# MKRFox1200V2_0.net
KiCad netlist of a schematic drawn in EAGLE
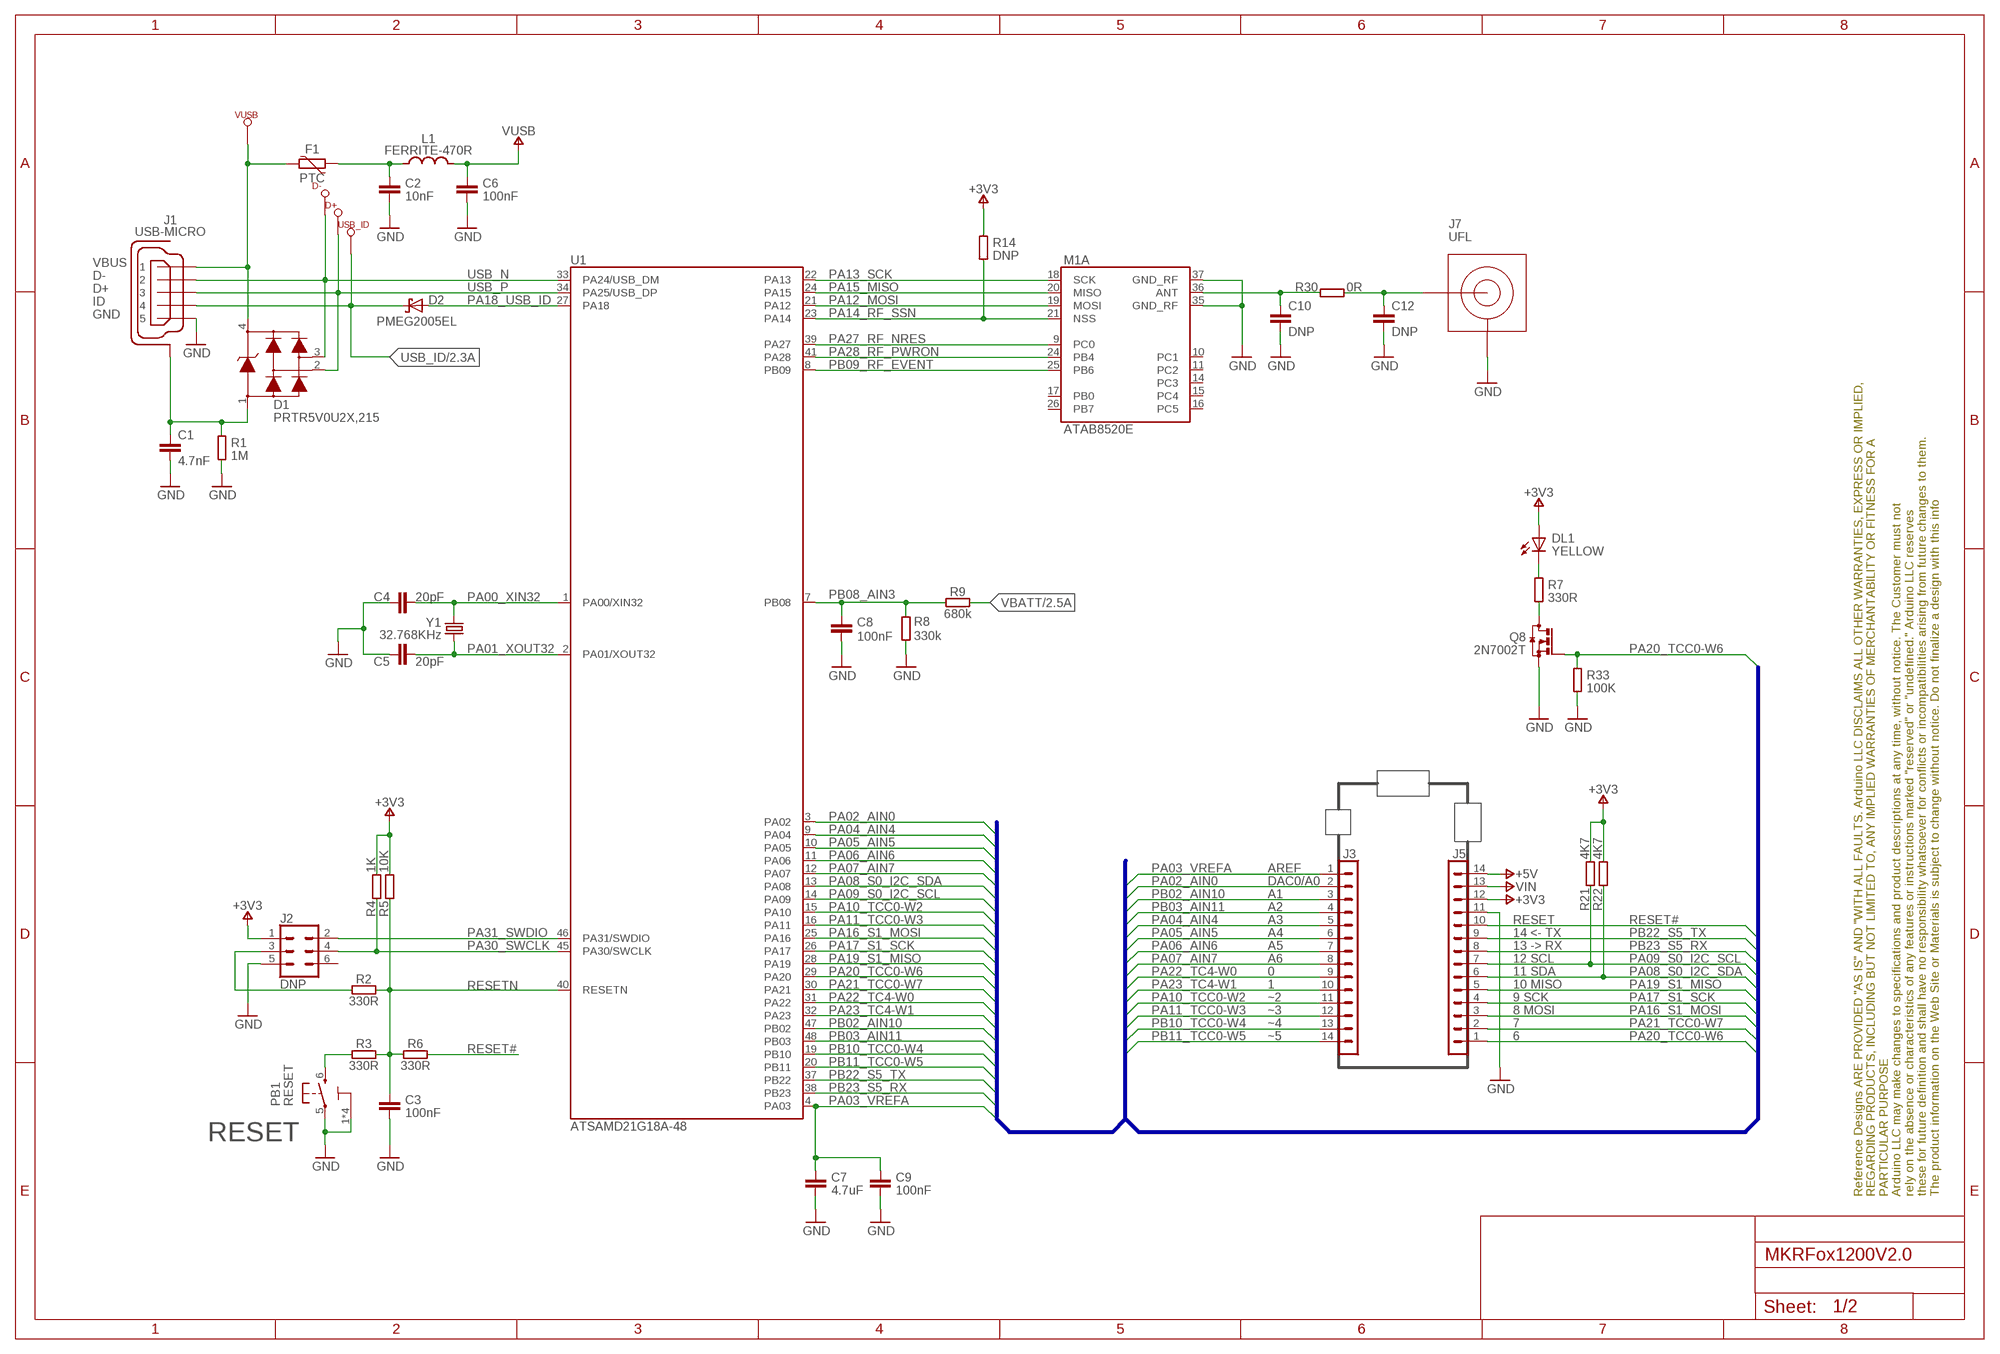
[diagram p0: schematic, sheet 1]
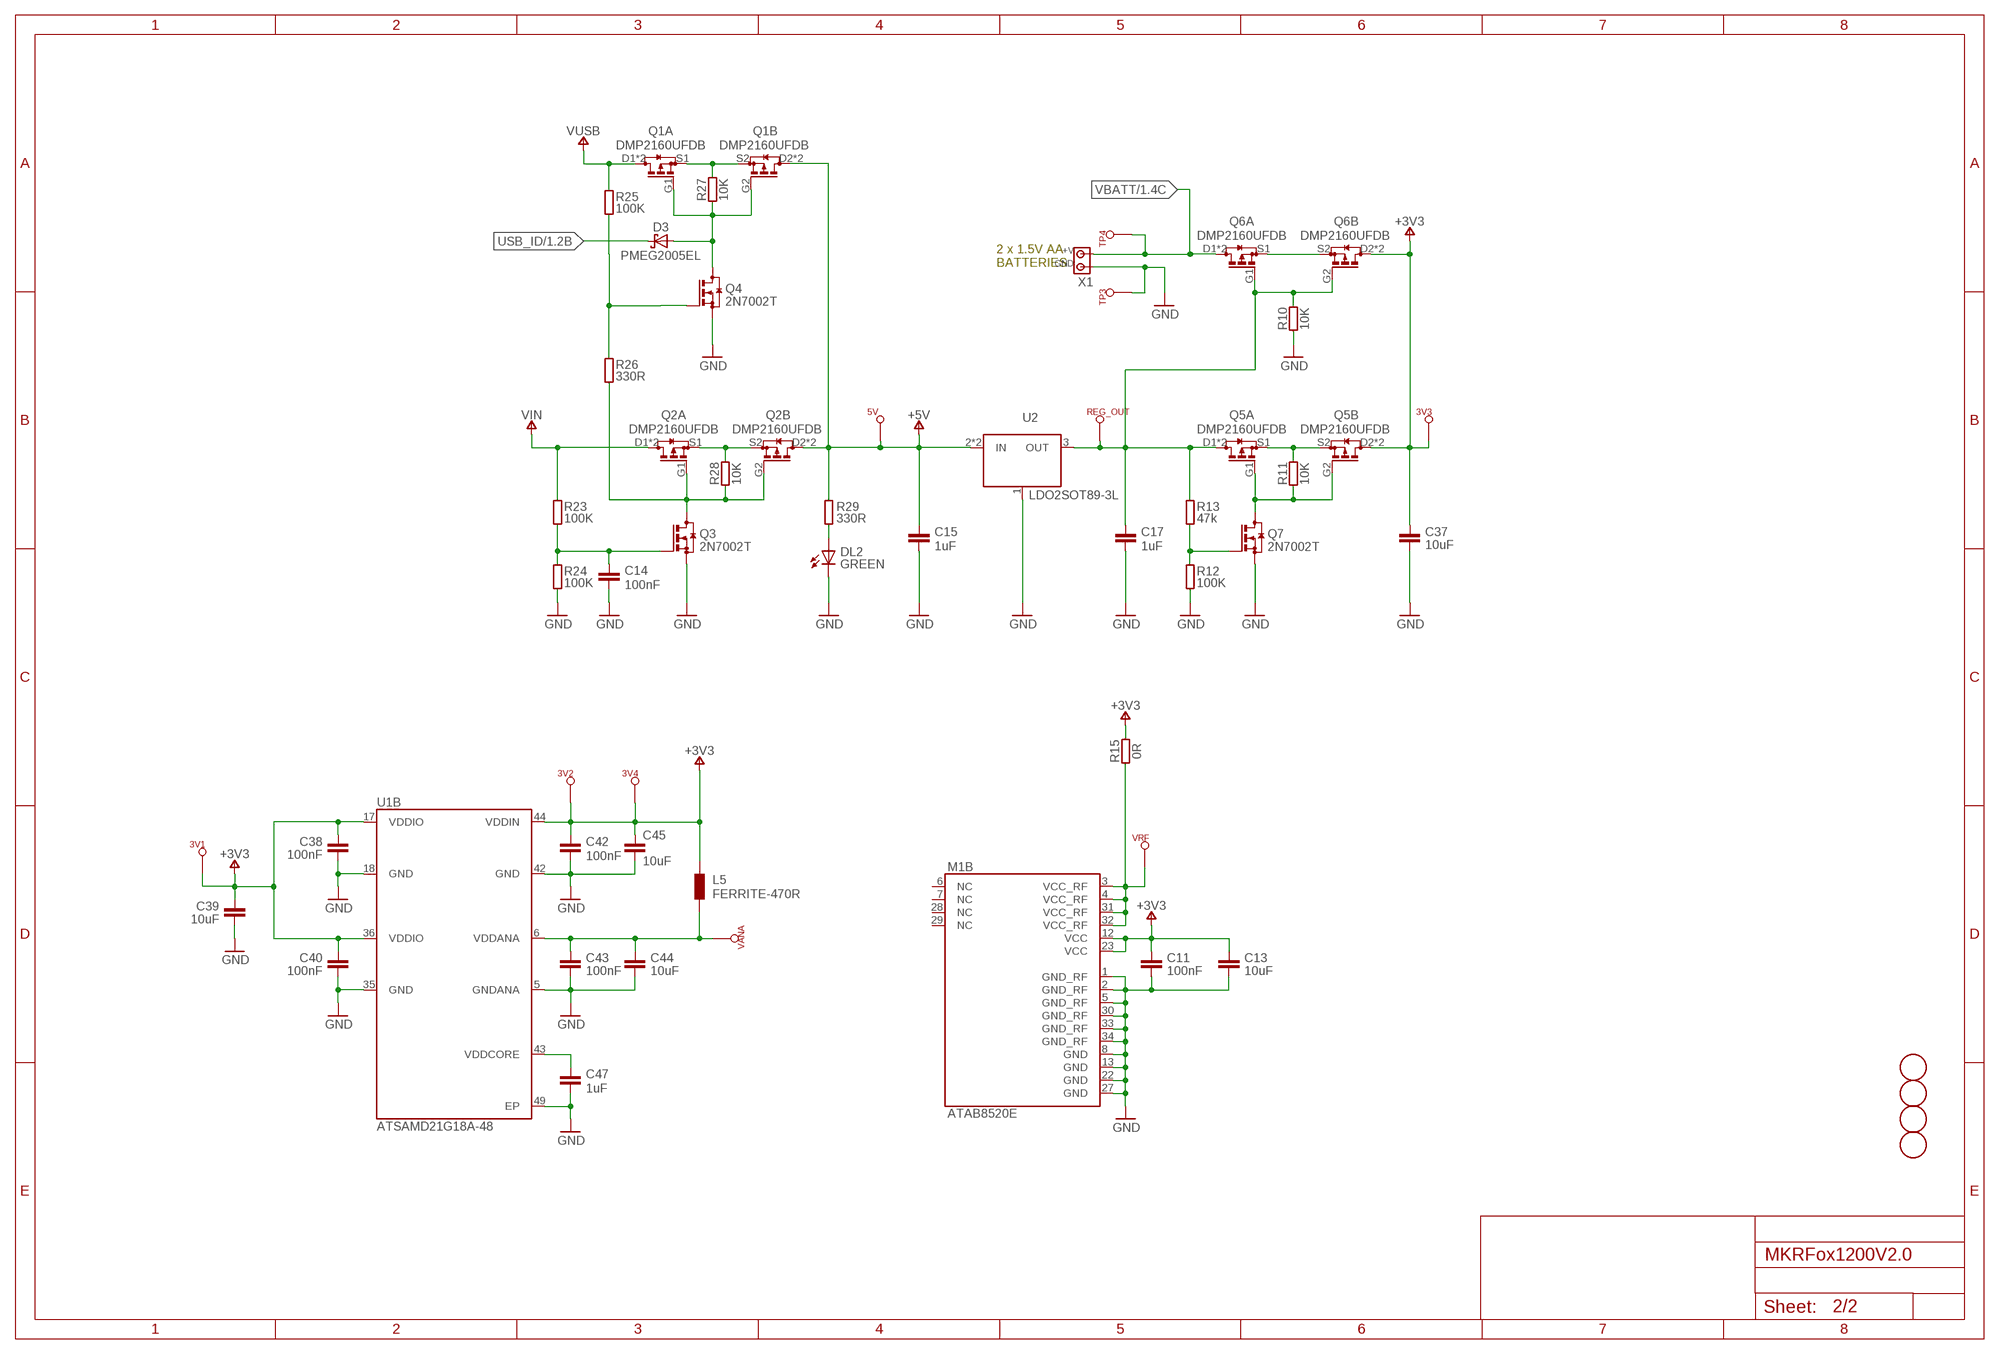
[diagram p1: schematic, sheet 2]

(export (version "E")
  (design (tool "Eeschema 10.0.6"))
  (components
    (comp (ref "C1")
      (value "4.7nF")
      (footprint "eagle-import:0805-R2013X50N")
      (fields (field (name "MANUFACTURER") "Kemet"))
      (libsource (lib "eagle-import") (part "C-08054.7NF"))
    )
    (comp (ref "C2")
      (value "10nF")
      (footprint "eagle-import:0402-1005X55N")
      (fields (field (name "MANUFACTURER") "Murata "))
      (libsource (lib "eagle-import") (part "C-0402-10NF"))
    )
    (comp (ref "C3")
      (value "100nF")
      (footprint "eagle-import:0402-1005X55N")
      (fields (field (name "MANUFACTURER") "TDK"))
      (libsource (lib "eagle-import") (part "C-0402-100NF"))
    )
    (comp (ref "C4")
      (value "20pF")
      (footprint "eagle-import:0402-1005X55N")
      (fields (field (name "MANUFACTURER") "Kemet"))
      (libsource (lib "eagle-import") (part "C-0402-20PF"))
    )
    (comp (ref "C5")
      (value "20pF")
      (footprint "eagle-import:0402-1005X55N")
      (fields (field (name "MANUFACTURER") "Kemet"))
      (libsource (lib "eagle-import") (part "C-0402-20PF"))
    )
    (comp (ref "C6")
      (value "100nF")
      (footprint "eagle-import:0402-1005X55N")
      (fields (field (name "MANUFACTURER") "TDK"))
      (libsource (lib "eagle-import") (part "C-0402-100NF"))
    )
    (comp (ref "C7")
      (value "4.7uF")
      (footprint "eagle-import:0402-1005X55N")
      (fields (field (name "MANUFACTURER") "Murata"))
      (libsource (lib "eagle-import") (part "C-0402-4.7UF"))
    )
    (comp (ref "C8")
      (value "100nF")
      (footprint "eagle-import:0402-1005X55N")
      (fields (field (name "MANUFACTURER") "TDK"))
      (libsource (lib "eagle-import") (part "C-0402-100NF"))
    )
    (comp (ref "C9")
      (value "100nF")
      (footprint "eagle-import:0402-1005X55N")
      (fields (field (name "MANUFACTURER") "TDK"))
      (libsource (lib "eagle-import") (part "C-0402-100NF"))
    )
    (comp (ref "C10")
      (value "DNP")
      (footprint "eagle-import:0402-1005X55N")
      (libsource (lib "eagle-import") (part "C-0402DNP"))
    )
    (comp (ref "C12")
      (value "DNP")
      (footprint "eagle-import:0402-1005X55N")
      (libsource (lib "eagle-import") (part "C-0402DNP"))
    )
    (comp (ref "D+")
      (value "TP1.00MM")
      (footprint "eagle-import:TP-1.00MM")
      (libsource (lib "eagle-import") (part "TP1.00MM"))
    )
    (comp (ref "D-")
      (value "TP1.00MM")
      (footprint "eagle-import:TP-1.00MM")
      (libsource (lib "eagle-import") (part "TP1.00MM"))
    )
    (comp (ref "D1")
      (value "PRTR5V0U2X,215")
      (footprint "eagle-import:SOT190P230X110-4N")
      (fields (field (name "MANUFACTURER") "NXP"))
      (libsource (lib "eagle-import") (part "PRTR5V0U2X,215"))
    )
    (comp (ref "D2")
      (value "PMEG2005EL")
      (footprint "eagle-import:SODFL1008X40N-882D")
      (fields (field (name "MANUFACTURER") "NXP"))
      (libsource (lib "eagle-import") (part "PMEG2005EL"))
    )
    (comp (ref "DL1")
      (value "YELLOW")
      (footprint "eagle-import:LEDC1608X80N-AK")
      (fields (field (name "MANUFACTURER") "Avago"))
      (libsource (lib "eagle-import") (part "LED-0603-YELLOW"))
    )
    (comp (ref "F1")
      (value "PTC")
      (footprint "eagle-import:0603-1608X90N")
      (fields (field (name "MANUFACTURER") "Bourns Inc "))
      (libsource (lib "eagle-import") (part "PTC"))
    )
    (comp (ref "FRAME1")
      (value "Page 1")
      (footprint "eagle-import:FRAME")
      (libsource (lib "eagle-import") (part "A3L-LOC"))
    )
    (comp (ref "J1")
      (value "USB-MICRO")
      (footprint "eagle-import:ZX62-AB-5PA")
      (fields (field (name "MANUFACTURER") "Hirose"))
      (libsource (lib "eagle-import") (part "USB-MICRO"))
    )
    (comp (ref "J2")
      (value "DNP")
      (footprint "eagle-import:2X3_SMT")
      (libsource (lib "eagle-import") (part "2X3_SMD_MALE"))
    )
    (comp (ref "J3")
      (value "DNP")
      (footprint "eagle-import:1X14_SMD_TH")
      (fields (field (name "MANUFACTURER") "ELDECO"))
      (libsource (lib "eagle-import") (part "PINHD-1X14-SMTH-SMD"))
    )
    (comp (ref "J5")
      (value "DNP")
      (footprint "eagle-import:1X14_SMD_TH")
      (fields (field (name "MANUFACTURER") "ELDECO"))
      (libsource (lib "eagle-import") (part "PINHD-1X14-SMTH-SMD"))
    )
    (comp (ref "J7")
      (value "UFL")
      (footprint "eagle-import:U.FL-R-SMT-1(60)")
      (fields (field (name "MANUFACTURER") "Hirose"))
      (libsource (lib "eagle-import") (part "UFL"))
    )
    (comp (ref "L1")
      (value "FERRITE-470R")
      (footprint "eagle-import:0603-1608X90N@1")
      (fields (field (name "MANUFACTURER") "Murata"))
      (libsource (lib "eagle-import") (part "Arduino-rcl_FERRITE-470R"))
    )
    (comp (ref "M1")
      (value "ATAB8520E")
      (footprint "eagle-import:ATAB8520E")
      (fields (field (name "MANUFACTURER") "Atmel"))
      (libsource (lib "eagle-import") (part "ATAB8520E"))
    )
    (comp (ref "PB1")
      (value "RESET")
      (footprint "eagle-import:C&K_PTS820_NO_HOLES")
      (fields (field (name "MANUFACTURER") "C&K"))
      (libsource (lib "eagle-import") (part "TACTILE1"))
    )
    (comp (ref "Q8")
      (value "2N7002T")
      (footprint "eagle-import:SOTFL50P160X78-3")
      (fields (field (name "MANUFACTURER") "Diodes Incorporated"))
      (libsource (lib "eagle-import") (part "2N7002T"))
    )
    (comp (ref "R1")
      (value "1M")
      (footprint "eagle-import:0402-1005X55N")
      (fields (field (name "MANUFACTURER") "Yageo"))
      (libsource (lib "eagle-import") (part "R-0402-1M"))
    )
    (comp (ref "R2")
      (value "330R")
      (footprint "eagle-import:0402-1005X55N")
      (fields (field (name "MANUFACTURER") "Yageo "))
      (libsource (lib "eagle-import") (part "R-0402-330R"))
    )
    (comp (ref "R3")
      (value "330R")
      (footprint "eagle-import:0402-1005X55N")
      (fields (field (name "MANUFACTURER") "Yageo "))
      (libsource (lib "eagle-import") (part "R-0402-330R"))
    )
    (comp (ref "R4")
      (value "1K")
      (footprint "eagle-import:0402-1005X55N")
      (fields (field (name "MANUFACTURER") "Yageo"))
      (libsource (lib "eagle-import") (part "R-0402-10K"))
    )
    (comp (ref "R5")
      (value "10K")
      (footprint "eagle-import:0402-1005X55N")
      (fields (field (name "MANUFACTURER") "Yageo"))
      (libsource (lib "eagle-import") (part "R-0402-10K"))
    )
    (comp (ref "R6")
      (value "330R")
      (footprint "eagle-import:0402-1005X55N")
      (fields (field (name "MANUFACTURER") "Yageo "))
      (libsource (lib "eagle-import") (part "R-0402-330R"))
    )
    (comp (ref "R7")
      (value "330R")
      (footprint "eagle-import:0402-1005X55N")
      (fields (field (name "MANUFACTURER") "Yageo "))
      (libsource (lib "eagle-import") (part "R-0402-330R"))
    )
    (comp (ref "R8")
      (value "330k")
      (footprint "eagle-import:0402-1005X55N")
      (fields (field (name "MANUFACTURER") "Yageo"))
      (libsource (lib "eagle-import") (part "R-0402-330K"))
    )
    (comp (ref "R9")
      (value "680k")
      (footprint "eagle-import:0402-1005X55N")
      (fields (field (name "MANUFACTURER") "Yageo"))
      (libsource (lib "eagle-import") (part "R-0402-680K"))
    )
    (comp (ref "R14")
      (value "DNP")
      (footprint "eagle-import:0402-1005X55N")
      (libsource (lib "eagle-import") (part "R-0402-DNP"))
    )
    (comp (ref "R21")
      (value "4K7")
      (footprint "eagle-import:0402-1005X55N")
      (fields (field (name "MANUFACTURER") "Yageo "))
      (libsource (lib "eagle-import") (part "R-0402-4K7"))
    )
    (comp (ref "R22")
      (value "4K7")
      (footprint "eagle-import:0402-1005X55N")
      (fields (field (name "MANUFACTURER") "Yageo "))
      (libsource (lib "eagle-import") (part "R-0402-4K7"))
    )
    (comp (ref "R30")
      (value "0R")
      (footprint "eagle-import:0402-1005X55N")
      (fields (field (name "MANUFACTURER") "Yageo"))
      (libsource (lib "eagle-import") (part "R-0402-0R"))
    )
    (comp (ref "R33")
      (value "100K")
      (footprint "eagle-import:0402-1005X55N")
      (fields (field (name "MANUFACTURER") "Yageo "))
      (libsource (lib "eagle-import") (part "R-0402-100K"))
    )
    (comp (ref "U1")
      (value "ATSAMD21G18A-48")
      (footprint "eagle-import:QFN50P700X700X90-49XN-EPSQ515")
      (fields (field (name "MANUFACTURER") "Atmel"))
      (libsource (lib "eagle-import") (part "ATSAMD21G18A-48"))
    )
    (comp (ref "USB_ID")
      (value "TP1.00MM")
      (footprint "eagle-import:TP-1.00MM")
      (libsource (lib "eagle-import") (part "TP1.00MM"))
    )
    (comp (ref "VUSB")
      (value "TP1.00MM")
      (footprint "eagle-import:TP-1.00MM")
      (libsource (lib "eagle-import") (part "TP1.00MM"))
    )
    (comp (ref "Y1")
      (value "32.768KHz")
      (footprint "eagle-import:ABS07")
      (fields (field (name "MANUFACTURER") "Abracon LLC"))
      (libsource (lib "eagle-import") (part "32.768KHZ"))
    )
    (comp (ref "3V1")
      (value "TP0.5MM")
      (footprint "eagle-import:TP-0.50MM")
      (libsource (lib "eagle-import") (part "TP0.5MM"))
    )
    (comp (ref "3V2")
      (value "TP0.5MM")
      (footprint "eagle-import:TP-0.50MM")
      (libsource (lib "eagle-import") (part "TP0.5MM"))
    )
    (comp (ref "3V3")
      (value "TP0.5MM")
      (footprint "eagle-import:TP-0.50MM")
      (libsource (lib "eagle-import") (part "TP0.5MM"))
    )
    (comp (ref "3V4")
      (value "TP0.5MM")
      (footprint "eagle-import:TP-0.50MM")
      (libsource (lib "eagle-import") (part "TP0.5MM"))
    )
    (comp (ref "5V")
      (value "TP0.5MM")
      (footprint "eagle-import:TP-0.50MM")
      (libsource (lib "eagle-import") (part "TP0.5MM"))
    )
    (comp (ref "C11")
      (value "100nF")
      (footprint "eagle-import:0402-1005X55N")
      (fields (field (name "MANUFACTURER") "TDK"))
      (libsource (lib "eagle-import") (part "C-0402-100NF"))
    )
    (comp (ref "C13")
      (value "10uF")
      (footprint "eagle-import:0603-1608X90N")
      (fields (field (name "MANUFACTURER") "Murata"))
      (libsource (lib "eagle-import") (part "C-0603-10UF"))
    )
    (comp (ref "C14")
      (value "100nF")
      (footprint "eagle-import:0402-1005X55N")
      (fields (field (name "MANUFACTURER") "TDK"))
      (libsource (lib "eagle-import") (part "C-0402-100NF"))
    )
    (comp (ref "C15")
      (value "1uF")
      (footprint "eagle-import:0402-1005X55N")
      (fields (field (name "MANUFACTURER") "Murata"))
      (libsource (lib "eagle-import") (part "C-0402-1UF"))
    )
    (comp (ref "C17")
      (value "1uF")
      (footprint "eagle-import:0402-1005X55N")
      (fields (field (name "MANUFACTURER") "Murata"))
      (libsource (lib "eagle-import") (part "C-0402-1UF"))
    )
    (comp (ref "C37")
      (value "10uF")
      (footprint "eagle-import:0603-1608X90N")
      (fields (field (name "MANUFACTURER") "Murata"))
      (libsource (lib "eagle-import") (part "C-0603-10UF"))
    )
    (comp (ref "C38")
      (value "100nF")
      (footprint "eagle-import:0402-1005X55N")
      (fields (field (name "MANUFACTURER") "TDK"))
      (libsource (lib "eagle-import") (part "C-0402-100NF"))
    )
    (comp (ref "C39")
      (value "10uF")
      (footprint "eagle-import:0603-1608X90N")
      (fields (field (name "MANUFACTURER") "Murata"))
      (libsource (lib "eagle-import") (part "C-0603-10UF"))
    )
    (comp (ref "C40")
      (value "100nF")
      (footprint "eagle-import:0402-1005X55N")
      (fields (field (name "MANUFACTURER") "TDK"))
      (libsource (lib "eagle-import") (part "C-0402-100NF"))
    )
    (comp (ref "C42")
      (value "100nF")
      (footprint "eagle-import:0402-1005X55N")
      (fields (field (name "MANUFACTURER") "TDK"))
      (libsource (lib "eagle-import") (part "C-0402-100NF"))
    )
    (comp (ref "C43")
      (value "100nF")
      (footprint "eagle-import:0402-1005X55N")
      (fields (field (name "MANUFACTURER") "TDK"))
      (libsource (lib "eagle-import") (part "C-0402-100NF"))
    )
    (comp (ref "C44")
      (value "10uF")
      (footprint "eagle-import:0603-1608X90N")
      (fields (field (name "MANUFACTURER") "Murata"))
      (libsource (lib "eagle-import") (part "C-0603-10UF"))
    )
    (comp (ref "C45")
      (value "10uF")
      (footprint "eagle-import:0603-1608X90N")
      (fields (field (name "MANUFACTURER") "Murata"))
      (libsource (lib "eagle-import") (part "C-0603-10UF"))
    )
    (comp (ref "C47")
      (value "1uF")
      (footprint "eagle-import:0402-1005X55N")
      (fields (field (name "MANUFACTURER") "Murata"))
      (libsource (lib "eagle-import") (part "C-0402-1UF"))
    )
    (comp (ref "D3")
      (value "PMEG2005EL")
      (footprint "eagle-import:SODFL1008X40N-882D")
      (fields (field (name "MANUFACTURER") "NXP"))
      (libsource (lib "eagle-import") (part "PMEG2005EL"))
    )
    (comp (ref "DL2")
      (value "GREEN")
      (footprint "eagle-import:LEDC1608X80N-AK")
      (fields (field (name "MANUFACTURER") "Avago "))
      (libsource (lib "eagle-import") (part "LED-0603-GREEN"))
    )
    (comp (ref "FD1")
      (value "FIDUCIAL-1.5MM")
      (footprint "eagle-import:FD-1-1.5")
      (fields (field (name "MANUFACTURER") "DNP"))
      (libsource (lib "eagle-import") (part "FIDUCIAL-1.5MM"))
    )
    (comp (ref "FD2")
      (value "FIDUCIAL-1.5MM")
      (footprint "eagle-import:FD-1-1.5")
      (fields (field (name "MANUFACTURER") "DNP"))
      (libsource (lib "eagle-import") (part "FIDUCIAL-1.5MM"))
    )
    (comp (ref "FD3")
      (value "FIDUCIAL-1.5MM")
      (footprint "eagle-import:FD-1-1.5")
      (fields (field (name "MANUFACTURER") "DNP"))
      (libsource (lib "eagle-import") (part "FIDUCIAL-1.5MM"))
    )
    (comp (ref "FD4")
      (value "FIDUCIAL-1.5MM")
      (footprint "eagle-import:FD-1-1.5")
      (fields (field (name "MANUFACTURER") "DNP"))
      (libsource (lib "eagle-import") (part "FIDUCIAL-1.5MM"))
    )
    (comp (ref "L5")
      (value "FERRITE-470R")
      (footprint "eagle-import:0603-1608X90N@1")
      (fields (field (name "MANUFACTURER") "Murata"))
      (libsource (lib "eagle-import") (part "Arduino-rcl_FERRITE-470R"))
    )
    (comp (ref "Q1")
      (value "DMP2160UFDB")
      (footprint "eagle-import:PWR_SC70")
      (fields (field (name "MANUFACTURER") "Diodes Inc"))
      (libsource (lib "eagle-import") (part "DMP2160UFDB"))
    )
    (comp (ref "Q2")
      (value "DMP2160UFDB")
      (footprint "eagle-import:PWR_SC70")
      (fields (field (name "MANUFACTURER") "Diodes Inc"))
      (libsource (lib "eagle-import") (part "DMP2160UFDB"))
    )
    (comp (ref "Q3")
      (value "2N7002T")
      (footprint "eagle-import:SOTFL50P160X78-3")
      (fields (field (name "MANUFACTURER") "Diodes Incorporated"))
      (libsource (lib "eagle-import") (part "2N7002T"))
    )
    (comp (ref "Q4")
      (value "2N7002T")
      (footprint "eagle-import:SOTFL50P160X78-3")
      (fields (field (name "MANUFACTURER") "Diodes Incorporated"))
      (libsource (lib "eagle-import") (part "2N7002T"))
    )
    (comp (ref "Q5")
      (value "DMP2160UFDB")
      (footprint "eagle-import:PWR_SC70")
      (fields (field (name "MANUFACTURER") "Diodes Inc"))
      (libsource (lib "eagle-import") (part "DMP2160UFDB"))
    )
    (comp (ref "Q6")
      (value "DMP2160UFDB")
      (footprint "eagle-import:PWR_SC70")
      (fields (field (name "MANUFACTURER") "Diodes Inc"))
      (libsource (lib "eagle-import") (part "DMP2160UFDB"))
    )
    (comp (ref "Q7")
      (value "2N7002T")
      (footprint "eagle-import:SOTFL50P160X78-3")
      (fields (field (name "MANUFACTURER") "Diodes Incorporated"))
      (libsource (lib "eagle-import") (part "2N7002T"))
    )
    (comp (ref "R10")
      (value "10K")
      (footprint "eagle-import:0402-1005X55N")
      (fields (field (name "MANUFACTURER") "Yageo"))
      (libsource (lib "eagle-import") (part "R-0402-10K"))
    )
    (comp (ref "R11")
      (value "10K")
      (footprint "eagle-import:0402-1005X55N")
      (fields (field (name "MANUFACTURER") "Yageo"))
      (libsource (lib "eagle-import") (part "R-0402-10K"))
    )
    (comp (ref "R12")
      (value "100K")
      (footprint "eagle-import:0402-1005X55N")
      (fields (field (name "MANUFACTURER") "Yageo "))
      (libsource (lib "eagle-import") (part "R-0402-100K"))
    )
    (comp (ref "R13")
      (value "47k")
      (footprint "eagle-import:0402-1005X55N")
      (fields (field (name "MANUFACTURER") "Yageo"))
      (libsource (lib "eagle-import") (part "R-0402-47K"))
    )
    (comp (ref "R15")
      (value "0R")
      (footprint "eagle-import:0402-1005X55N")
      (fields (field (name "MANUFACTURER") "Yageo"))
      (libsource (lib "eagle-import") (part "R-0402-0R"))
    )
    (comp (ref "R23")
      (value "100K")
      (footprint "eagle-import:0402-1005X55N")
      (fields (field (name "MANUFACTURER") "Yageo "))
      (libsource (lib "eagle-import") (part "R-0402-100K"))
    )
    (comp (ref "R24")
      (value "100K")
      (footprint "eagle-import:0402-1005X55N")
      (fields (field (name "MANUFACTURER") "Yageo "))
      (libsource (lib "eagle-import") (part "R-0402-100K"))
    )
    (comp (ref "R25")
      (value "100K")
      (footprint "eagle-import:0402-1005X55N")
      (fields (field (name "MANUFACTURER") "Yageo "))
      (libsource (lib "eagle-import") (part "R-0402-100K"))
    )
    (comp (ref "R26")
      (value "330R")
      (footprint "eagle-import:0402-1005X55N")
      (fields (field (name "MANUFACTURER") "Yageo "))
      (libsource (lib "eagle-import") (part "R-0402-330R"))
    )
    (comp (ref "R27")
      (value "10K")
      (footprint "eagle-import:0402-1005X55N")
      (fields (field (name "MANUFACTURER") "Yageo"))
      (libsource (lib "eagle-import") (part "R-0402-10K"))
    )
    (comp (ref "R28")
      (value "10K")
      (footprint "eagle-import:0402-1005X55N")
      (fields (field (name "MANUFACTURER") "Yageo"))
      (libsource (lib "eagle-import") (part "R-0402-10K"))
    )
    (comp (ref "R29")
      (value "330R")
      (footprint "eagle-import:0402-1005X55N")
      (fields (field (name "MANUFACTURER") "Yageo "))
      (libsource (lib "eagle-import") (part "R-0402-330R"))
    )
    (comp (ref "REG_OUT")
      (value "TP0.5MM")
      (footprint "eagle-import:TP-0.50MM")
      (libsource (lib "eagle-import") (part "TP0.5MM"))
    )
    (comp (ref "TP3")
      (value "TP1.00MM")
      (footprint "eagle-import:TP-1.00MM")
      (libsource (lib "eagle-import") (part "TP1.00MM"))
    )
    (comp (ref "TP4")
      (value "TP1.00MM")
      (footprint "eagle-import:TP-1.00MM")
      (libsource (lib "eagle-import") (part "TP1.00MM"))
    )
    (comp (ref "U2")
      (value "LDO2SOT89-3L")
      (footprint "eagle-import:SOT89-3L")
      (fields (field (name "MANUFACTURER") "Diodes Inc"))
      (libsource (lib "eagle-import") (part "LDO2SOT89-3L"))
    )
    (comp (ref "VANA")
      (value "TP0.5MM")
      (footprint "eagle-import:TP-0.50MM")
      (libsource (lib "eagle-import") (part "TP0.5MM"))
    )
    (comp (ref "VRF")
      (value "TP0.5MM")
      (footprint "eagle-import:TP-0.50MM")
      (libsource (lib "eagle-import") (part "TP0.5MM"))
    )
    (comp (ref "X1")
      (value "SCREW2X2.54")
      (footprint "eagle-import:SCREW2")
      (fields (field (name "MANUFACTURER") "On Shore Technology Inc."))
      (libsource (lib "eagle-import") (part "SCREW2X2.54"))
    )
  )
  (nets
    (net (code "1") (name "+3V3") (class "Default")
      (node (ref "3V1") (pin "X") (pinfunction "TESTP_X") (pintype "passive"))
      (node (ref "3V2") (pin "X") (pinfunction "TESTP_X") (pintype "passive"))
      (node (ref "3V3") (pin "X") (pinfunction "TESTP_X") (pintype "passive"))
      (node (ref "3V4") (pin "X") (pinfunction "TESTP_X") (pintype "passive"))
      (node (ref "C11") (pin "1") (pinfunction "1_1") (pintype "passive"))
      (node (ref "C13") (pin "1") (pinfunction "1_1") (pintype "passive"))
      (node (ref "C37") (pin "1") (pinfunction "1_1") (pintype "passive"))
      (node (ref "C38") (pin "1") (pinfunction "1_1") (pintype "passive"))
      (node (ref "C39") (pin "1") (pinfunction "1_1") (pintype "passive"))
      (node (ref "C40") (pin "1") (pinfunction "1_1") (pintype "passive"))
      (node (ref "C42") (pin "1") (pinfunction "1_1") (pintype "passive"))
      (node (ref "C45") (pin "1") (pinfunction "1_1") (pintype "passive"))
      (node (ref "DL1") (pin "A") (pinfunction "A_A") (pintype "passive"))
      (node (ref "J2") (pin "1") (pinfunction "1_1") (pintype "passive"))
      (node (ref "J5") (pin "12") (pinfunction "12_12") (pintype "passive"))
      (node (ref "L5") (pin "1") (pinfunction "1_1") (pintype "passive"))
      (node (ref "M1") (pin "12") (pinfunction "VCC_12") (pintype "bidirectional"))
      (node (ref "M1") (pin "23") (pinfunction "VCC_23") (pintype "bidirectional"))
      (node (ref "Q5") (pin "D2") (pinfunction "D_D2") (pintype "passive"))
      (node (ref "Q5") (pin "D2'") (pinfunction "D_D2'") (pintype "passive"))
      (node (ref "Q6") (pin "D2") (pinfunction "D_D2") (pintype "passive"))
      (node (ref "Q6") (pin "D2'") (pinfunction "D_D2'") (pintype "passive"))
      (node (ref "R14") (pin "2") (pinfunction "2_2") (pintype "passive"))
      (node (ref "R15") (pin "2") (pinfunction "2_2") (pintype "passive"))
      (node (ref "R21") (pin "2") (pinfunction "2_2") (pintype "passive"))
      (node (ref "R22") (pin "2") (pinfunction "2_2") (pintype "passive"))
      (node (ref "R4") (pin "2") (pinfunction "2_2") (pintype "passive"))
      (node (ref "R5") (pin "2") (pinfunction "2_2") (pintype "passive"))
      (node (ref "U1") (pin "17") (pinfunction "VDDIO_17") (pintype "power_in"))
      (node (ref "U1") (pin "36") (pinfunction "VDDIO_36") (pintype "power_in"))
      (node (ref "U1") (pin "44") (pinfunction "VDDIN_44") (pintype "power_in"))
    )
    (net (code "2") (name "+5V") (class "Default")
      (node (ref "5V") (pin "X") (pinfunction "TESTP_X") (pintype "passive"))
      (node (ref "C15") (pin "1") (pinfunction "1_1") (pintype "passive"))
      (node (ref "J5") (pin "14") (pinfunction "14_14") (pintype "passive"))
      (node (ref "Q1") (pin "D2") (pinfunction "D_D2") (pintype "passive"))
      (node (ref "Q1") (pin "D2'") (pinfunction "D_D2'") (pintype "passive"))
      (node (ref "Q2") (pin "D2") (pinfunction "D_D2") (pintype "passive"))
      (node (ref "Q2") (pin "D2'") (pinfunction "D_D2'") (pintype "passive"))
      (node (ref "R29") (pin "2") (pinfunction "2_2") (pintype "passive"))
      (node (ref "U2") (pin "2") (pinfunction "IN_2") (pintype "input"))
      (node (ref "U2") (pin "TH") (pinfunction "IN_TH") (pintype "input"))
    )
    (net (code "3") (name "GND") (class "Default")
      (node (ref "C1") (pin "2") (pinfunction "2_2") (pintype "passive"))
      (node (ref "C10") (pin "2") (pinfunction "2_2") (pintype "passive"))
      (node (ref "C11") (pin "2") (pinfunction "2_2") (pintype "passive"))
      (node (ref "C12") (pin "2") (pinfunction "2_2") (pintype "passive"))
      (node (ref "C13") (pin "2") (pinfunction "2_2") (pintype "passive"))
      (node (ref "C14") (pin "2") (pinfunction "2_2") (pintype "passive"))
      (node (ref "C15") (pin "2") (pinfunction "2_2") (pintype "passive"))
      (node (ref "C17") (pin "2") (pinfunction "2_2") (pintype "passive"))
      (node (ref "C2") (pin "2") (pinfunction "2_2") (pintype "passive"))
      (node (ref "C3") (pin "2") (pinfunction "2_2") (pintype "passive"))
      (node (ref "C37") (pin "2") (pinfunction "2_2") (pintype "passive"))
      (node (ref "C38") (pin "2") (pinfunction "2_2") (pintype "passive"))
      (node (ref "C39") (pin "2") (pinfunction "2_2") (pintype "passive"))
      (node (ref "C4") (pin "1") (pinfunction "1_1") (pintype "passive"))
      (node (ref "C40") (pin "2") (pinfunction "2_2") (pintype "passive"))
      (node (ref "C42") (pin "2") (pinfunction "2_2") (pintype "passive"))
      (node (ref "C43") (pin "2") (pinfunction "2_2") (pintype "passive"))
      (node (ref "C44") (pin "2") (pinfunction "2_2") (pintype "passive"))
      (node (ref "C45") (pin "2") (pinfunction "2_2") (pintype "passive"))
      (node (ref "C47") (pin "2") (pinfunction "2_2") (pintype "passive"))
      (node (ref "C5") (pin "1") (pinfunction "1_1") (pintype "passive"))
      (node (ref "C6") (pin "2") (pinfunction "2_2") (pintype "passive"))
      (node (ref "C7") (pin "2") (pinfunction "2_2") (pintype "passive"))
      (node (ref "C8") (pin "2") (pinfunction "2_2") (pintype "passive"))
      (node (ref "C9") (pin "2") (pinfunction "2_2") (pintype "passive"))
      (node (ref "DL2") (pin "C") (pinfunction "C_C") (pintype "passive"))
      (node (ref "J1") (pin "5") (pinfunction "5_5") (pintype "passive"))
      (node (ref "J2") (pin "5") (pinfunction "5_5") (pintype "passive"))
      (node (ref "J5") (pin "11") (pinfunction "11_11") (pintype "passive"))
      (node (ref "J7") (pin "GND1") (pinfunction "GND_GND1") (pintype "bidirectional"))
      (node (ref "J7") (pin "GND2") (pinfunction "GND_GND2") (pintype "bidirectional"))
      (node (ref "M1") (pin "1") (pinfunction "GND_RF_1") (pintype "power_in"))
      (node (ref "M1") (pin "13") (pinfunction "GND_13") (pintype "power_in"))
      (node (ref "M1") (pin "2") (pinfunction "GND_RF_2") (pintype "power_in"))
      (node (ref "M1") (pin "22") (pinfunction "GND_22") (pintype "power_in"))
      (node (ref "M1") (pin "27") (pinfunction "GND_27") (pintype "power_in"))
      (node (ref "M1") (pin "30") (pinfunction "GND_RF_30") (pintype "power_in"))
      (node (ref "M1") (pin "33") (pinfunction "GND_RF_33") (pintype "power_in"))
      (node (ref "M1") (pin "34") (pinfunction "GND_RF_34") (pintype "power_in"))
      (node (ref "M1") (pin "35") (pinfunction "GND_RF_35") (pintype "power_in"))
      (node (ref "M1") (pin "37") (pinfunction "GND_RF_37") (pintype "power_in"))
      (node (ref "M1") (pin "5") (pinfunction "GND_RF_5") (pintype "power_in"))
      (node (ref "M1") (pin "8") (pinfunction "GND_8") (pintype "power_in"))
      (node (ref "PB1") (pin "1") (pinfunction "3_1") (pintype "power_in"))
      (node (ref "PB1") (pin "2") (pinfunction "3_2") (pintype "power_in"))
      (node (ref "PB1") (pin "3") (pinfunction "3_3") (pintype "power_in"))
      (node (ref "PB1") (pin "4") (pinfunction "3_4") (pintype "power_in"))
      (node (ref "PB1") (pin "5") (pinfunction "1_5") (pintype "passive"))
      (node (ref "Q3") (pin "S") (pinfunction "S_S") (pintype "passive"))
      (node (ref "Q4") (pin "S") (pinfunction "S_S") (pintype "passive"))
      (node (ref "Q7") (pin "S") (pinfunction "S_S") (pintype "passive"))
      (node (ref "Q8") (pin "S") (pinfunction "S_S") (pintype "passive"))
      (node (ref "R1") (pin "1") (pinfunction "1_1") (pintype "passive"))
      (node (ref "R10") (pin "1") (pinfunction "1_1") (pintype "passive"))
      (node (ref "R12") (pin "1") (pinfunction "1_1") (pintype "passive"))
      (node (ref "R24") (pin "1") (pinfunction "1_1") (pintype "passive"))
      (node (ref "R33") (pin "1") (pinfunction "1_1") (pintype "passive"))
      (node (ref "R8") (pin "1") (pinfunction "1_1") (pintype "passive"))
      (node (ref "TP3") (pin "X") (pinfunction "TESTP_X") (pintype "passive"))
      (node (ref "U1") (pin "18") (pinfunction "GND_18") (pintype "power_in"))
      (node (ref "U1") (pin "35") (pinfunction "GND_35") (pintype "power_in"))
      (node (ref "U1") (pin "42") (pinfunction "GND_42") (pintype "power_in"))
      (node (ref "U1") (pin "49") (pinfunction "EP_49") (pintype "passive"))
      (node (ref "U1") (pin "5") (pinfunction "GNDANA_5") (pintype "power_in"))
      (node (ref "U2") (pin "1") (pinfunction "GND/ADJ_1") (pintype "input"))
      (node (ref "X1") (pin "GND") (pinfunction "GND_GND") (pintype "passive"))
    )
    (net (code "4") (name "Net-(C1-Pad1)") (class "Default")
      (node (ref "C1") (pin "1") (pinfunction "1_1") (pintype "passive"))
      (node (ref "D1") (pin "1") (pinfunction "1_1") (pintype "passive"))
      (node (ref "J1") (pin "10") (pinfunction "SH_10") (pintype "passive"))
      (node (ref "J1") (pin "11") (pinfunction "SH_11") (pintype "passive"))
      (node (ref "J1") (pin "6") (pinfunction "SH_6") (pintype "passive"))
      (node (ref "J1") (pin "7") (pinfunction "SH_7") (pintype "passive"))
      (node (ref "J1") (pin "8") (pinfunction "SH_8") (pintype "passive"))
      (node (ref "J1") (pin "9") (pinfunction "SH_9") (pintype "passive"))
      (node (ref "R1") (pin "2") (pinfunction "2_2") (pintype "passive"))
    )
    (net (code "5") (name "Net-(C2-Pad1)") (class "Default")
      (node (ref "C2") (pin "1") (pinfunction "1_1") (pintype "passive"))
      (node (ref "F1") (pin "1") (pinfunction "1_1") (pintype "passive"))
      (node (ref "L1") (pin "1") (pinfunction "1_1") (pintype "passive"))
    )
    (net (code "6") (name "Net-(C12-Pad1)") (class "Default")
      (node (ref "C12") (pin "1") (pinfunction "1_1") (pintype "passive"))
      (node (ref "J7") (pin "SIG") (pinfunction "SIG_SIG") (pintype "bidirectional"))
      (node (ref "R30") (pin "2") (pinfunction "2_2") (pintype "passive"))
    )
    (net (code "7") (name "Net-(C14-Pad1)") (class "Default")
      (node (ref "C14") (pin "1") (pinfunction "1_1") (pintype "passive"))
      (node (ref "Q3") (pin "G") (pinfunction "G_G") (pintype "passive"))
      (node (ref "R23") (pin "1") (pinfunction "1_1") (pintype "passive"))
      (node (ref "R24") (pin "2") (pinfunction "2_2") (pintype "passive"))
    )
    (net (code "8") (name "Net-(DL1-PadC)") (class "Default")
      (node (ref "DL1") (pin "C") (pinfunction "C_C") (pintype "passive"))
      (node (ref "R7") (pin "2") (pinfunction "2_2") (pintype "passive"))
    )
    (net (code "9") (name "Net-(DL2-PadA)") (class "Default")
      (node (ref "DL2") (pin "A") (pinfunction "A_A") (pintype "passive"))
      (node (ref "R29") (pin "1") (pinfunction "1_1") (pintype "passive"))
    )
    (net (code "10") (name "Net-(J2-Pad3)") (class "Default")
      (node (ref "J2") (pin "3") (pinfunction "3_3") (pintype "passive"))
      (node (ref "R2") (pin "1") (pinfunction "1_1") (pintype "passive"))
    )
    (net (code "11") (name "Net-(M1A-ANT)") (class "Default")
      (node (ref "C10") (pin "1") (pinfunction "1_1") (pintype "passive"))
      (node (ref "M1") (pin "36") (pinfunction "ANT_36") (pintype "bidirectional"))
      (node (ref "R30") (pin "1") (pinfunction "1_1") (pintype "passive"))
    )
    (net (code "12") (name "Net-(PB1-2)") (class "Default")
      (node (ref "PB1") (pin "6") (pinfunction "2_6") (pintype "passive"))
      (node (ref "R3") (pin "1") (pinfunction "1_1") (pintype "passive"))
    )
    (net (code "13") (name "Net-(Q1A-G)") (class "Default")
      (node (ref "D3") (pin "A") (pinfunction "A_A") (pintype "passive"))
      (node (ref "Q1") (pin "G1") (pinfunction "G_G1") (pintype "passive"))
      (node (ref "Q1") (pin "G2") (pinfunction "G_G2") (pintype "passive"))
      (node (ref "Q4") (pin "D") (pinfunction "D_D") (pintype "passive"))
      (node (ref "R27") (pin "1") (pinfunction "1_1") (pintype "passive"))
    )
    (net (code "14") (name "Net-(Q1A-S)") (class "Default")
      (node (ref "Q1") (pin "S1") (pinfunction "S_S1") (pintype "passive"))
      (node (ref "Q1") (pin "S2") (pinfunction "S_S2") (pintype "passive"))
      (node (ref "R27") (pin "2") (pinfunction "2_2") (pintype "passive"))
    )
    (net (code "15") (name "Net-(Q2A-G)") (class "Default")
      (node (ref "Q2") (pin "G1") (pinfunction "G_G1") (pintype "passive"))
      (node (ref "Q2") (pin "G2") (pinfunction "G_G2") (pintype "passive"))
      (node (ref "Q3") (pin "D") (pinfunction "D_D") (pintype "passive"))
      (node (ref "R26") (pin "1") (pinfunction "1_1") (pintype "passive"))
      (node (ref "R28") (pin "1") (pinfunction "1_1") (pintype "passive"))
    )
    (net (code "16") (name "Net-(Q2A-S)") (class "Default")
      (node (ref "Q2") (pin "S1") (pinfunction "S_S1") (pintype "passive"))
      (node (ref "Q2") (pin "S2") (pinfunction "S_S2") (pintype "passive"))
      (node (ref "R28") (pin "2") (pinfunction "2_2") (pintype "passive"))
    )
    (net (code "17") (name "Net-(Q4-PadG)") (class "Default")
      (node (ref "Q4") (pin "G") (pinfunction "G_G") (pintype "passive"))
      (node (ref "R25") (pin "1") (pinfunction "1_1") (pintype "passive"))
      (node (ref "R26") (pin "2") (pinfunction "2_2") (pintype "passive"))
    )
    (net (code "18") (name "Net-(Q5A-G)") (class "Default")
      (node (ref "Q5") (pin "G1") (pinfunction "G_G1") (pintype "passive"))
      (node (ref "Q5") (pin "G2") (pinfunction "G_G2") (pintype "passive"))
      (node (ref "Q7") (pin "D") (pinfunction "D_D") (pintype "passive"))
      (node (ref "R11") (pin "1") (pinfunction "1_1") (pintype "passive"))
    )
    (net (code "19") (name "Net-(Q5A-S)") (class "Default")
      (node (ref "Q5") (pin "S1") (pinfunction "S_S1") (pintype "passive"))
      (node (ref "Q5") (pin "S2") (pinfunction "S_S2") (pintype "passive"))
      (node (ref "R11") (pin "2") (pinfunction "2_2") (pintype "passive"))
    )
    (net (code "20") (name "Net-(Q6A-G)") (class "Default")
      (node (ref "C17") (pin "1") (pinfunction "1_1") (pintype "passive"))
      (node (ref "Q5") (pin "D1") (pinfunction "D_D1") (pintype "passive"))
      (node (ref "Q5") (pin "D1'") (pinfunction "D_D1'") (pintype "passive"))
      (node (ref "Q6") (pin "G1") (pinfunction "G_G1") (pintype "passive"))
      (node (ref "Q6") (pin "G2") (pinfunction "G_G2") (pintype "passive"))
      (node (ref "R10") (pin "2") (pinfunction "2_2") (pintype "passive"))
      (node (ref "R13") (pin "2") (pinfunction "2_2") (pintype "passive"))
      (node (ref "REG_OUT") (pin "X") (pinfunction "TESTP_X") (pintype "passive"))
      (node (ref "U2") (pin "3") (pinfunction "OUT_3") (pintype "passive"))
    )
    (net (code "21") (name "Net-(Q6A-S)") (class "Default")
      (node (ref "Q6") (pin "S1") (pinfunction "S_S1") (pintype "passive"))
      (node (ref "Q6") (pin "S2") (pinfunction "S_S2") (pintype "passive"))
    )
    (net (code "22") (name "Net-(Q7-PadG)") (class "Default")
      (node (ref "Q7") (pin "G") (pinfunction "G_G") (pintype "passive"))
      (node (ref "R12") (pin "2") (pinfunction "2_2") (pintype "passive"))
      (node (ref "R13") (pin "1") (pinfunction "1_1") (pintype "passive"))
    )
    (net (code "23") (name "Net-(Q8-PadD)") (class "Default")
      (node (ref "Q8") (pin "D") (pinfunction "D_D") (pintype "passive"))
      (node (ref "R7") (pin "1") (pinfunction "1_1") (pintype "passive"))
    )
    (net (code "24") (name "Net-(U1B-VDDANA)") (class "Default")
      (node (ref "C43") (pin "1") (pinfunction "1_1") (pintype "passive"))
      (node (ref "C44") (pin "1") (pinfunction "1_1") (pintype "passive"))
      (node (ref "L5") (pin "2") (pinfunction "2_2") (pintype "passive"))
      (node (ref "U1") (pin "6") (pinfunction "VDDANA_6") (pintype "power_in"))
      (node (ref "VANA") (pin "X") (pinfunction "TESTP_X") (pintype "passive"))
    )
    (net (code "25") (name "Net-(U1B-VDDCORE)") (class "Default")
      (node (ref "C47") (pin "1") (pinfunction "1_1") (pintype "passive"))
      (node (ref "U1") (pin "43") (pinfunction "VDDCORE_43") (pintype "power_in"))
    )
    (net (code "26") (name "Net-(VRF-TESTP)") (class "Default")
      (node (ref "M1") (pin "3") (pinfunction "VCC_RF_3") (pintype "power_in"))
      (node (ref "M1") (pin "31") (pinfunction "VCC_RF_31") (pintype "power_in"))
      (node (ref "M1") (pin "32") (pinfunction "VCC_RF_32") (pintype "power_in"))
      (node (ref "M1") (pin "4") (pinfunction "VCC_RF_4") (pintype "power_in"))
      (node (ref "R15") (pin "1") (pinfunction "1_1") (pintype "passive"))
      (node (ref "VRF") (pin "X") (pinfunction "TESTP_X") (pintype "passive"))
    )
    (net (code "27") (name "Net-(VUSB-TESTP)") (class "Default")
      (node (ref "D1") (pin "4") (pinfunction "4_4") (pintype "passive"))
      (node (ref "F1") (pin "2") (pinfunction "2_2") (pintype "passive"))
      (node (ref "J1") (pin "1") (pinfunction "1_1") (pintype "passive"))
      (node (ref "VUSB") (pin "X") (pinfunction "TESTP_X") (pintype "passive"))
    )
    (net (code "28") (name "PA00_XIN32") (class "Default")
      (node (ref "C4") (pin "2") (pinfunction "2_2") (pintype "passive"))
      (node (ref "U1") (pin "1") (pinfunction "PA00/XIN32_1") (pintype "bidirectional"))
      (node (ref "Y1") (pin "2") (pinfunction "2_2") (pintype "passive"))
    )
    (net (code "29") (name "PA01_XOUT32") (class "Default")
      (node (ref "C5") (pin "2") (pinfunction "2_2") (pintype "passive"))
      (node (ref "U1") (pin "2") (pinfunction "PA01/XOUT32_2") (pintype "bidirectional"))
      (node (ref "Y1") (pin "1") (pinfunction "1_1") (pintype "passive"))
    )
    (net (code "30") (name "PA02_AIN0") (class "Default")
      (node (ref "J3") (pin "2") (pinfunction "2_2") (pintype "passive"))
      (node (ref "U1") (pin "3") (pinfunction "PA02_3") (pintype "bidirectional"))
    )
    (net (code "31") (name "PA03_VREFA") (class "Default")
      (node (ref "C7") (pin "1") (pinfunction "1_1") (pintype "passive"))
      (node (ref "C9") (pin "1") (pinfunction "1_1") (pintype "passive"))
      (node (ref "J3") (pin "1") (pinfunction "1_1") (pintype "passive"))
      (node (ref "U1") (pin "4") (pinfunction "PA03_4") (pintype "bidirectional"))
    )
    (net (code "32") (name "PA04_AIN4") (class "Default")
      (node (ref "J3") (pin "5") (pinfunction "5_5") (pintype "passive"))
      (node (ref "U1") (pin "9") (pinfunction "PA04_9") (pintype "bidirectional"))
    )
    (net (code "33") (name "PA05_AIN5") (class "Default")
      (node (ref "J3") (pin "6") (pinfunction "6_6") (pintype "passive"))
      (node (ref "U1") (pin "10") (pinfunction "PA05_10") (pintype "bidirectional"))
    )
    (net (code "34") (name "PA06_AIN6") (class "Default")
      (node (ref "J3") (pin "7") (pinfunction "7_7") (pintype "passive"))
      (node (ref "U1") (pin "11") (pinfunction "PA06_11") (pintype "bidirectional"))
    )
    (net (code "35") (name "PA07_AIN7") (class "Default")
      (node (ref "J3") (pin "8") (pinfunction "8_8") (pintype "passive"))
      (node (ref "U1") (pin "12") (pinfunction "PA07_12") (pintype "bidirectional"))
    )
    (net (code "36") (name "PA08_S0_I2C_SDA") (class "Default")
      (node (ref "J5") (pin "6") (pinfunction "6_6") (pintype "passive"))
      (node (ref "R22") (pin "1") (pinfunction "1_1") (pintype "passive"))
      (node (ref "U1") (pin "13") (pinfunction "PA08_13") (pintype "bidirectional"))
    )
    (net (code "37") (name "PA09_S0_I2C_SCL") (class "Default")
      (node (ref "J5") (pin "7") (pinfunction "7_7") (pintype "passive"))
      (node (ref "R21") (pin "1") (pinfunction "1_1") (pintype "passive"))
      (node (ref "U1") (pin "14") (pinfunction "PA09_14") (pintype "bidirectional"))
    )
    (net (code "38") (name "PA10_TCC0-W2") (class "Default")
      (node (ref "J3") (pin "11") (pinfunction "11_11") (pintype "passive"))
      (node (ref "U1") (pin "15") (pinfunction "PA10_15") (pintype "bidirectional"))
    )
    (net (code "39") (name "PA11_TCC0-W3") (class "Default")
      (node (ref "J3") (pin "12") (pinfunction "12_12") (pintype "passive"))
      (node (ref "U1") (pin "16") (pinfunction "PA11_16") (pintype "bidirectional"))
    )
    (net (code "40") (name "PA12_MOSI") (class "Default")
      (node (ref "M1") (pin "19") (pinfunction "MOSI_19") (pintype "bidirectional"))
      (node (ref "U1") (pin "21") (pinfunction "PA12_21") (pintype "bidirectional"))
    )
    (net (code "41") (name "PA13_SCK") (class "Default")
      (node (ref "M1") (pin "18") (pinfunction "SCK_18") (pintype "bidirectional"))
      (node (ref "U1") (pin "22") (pinfunction "PA13_22") (pintype "bidirectional"))
    )
    (net (code "42") (name "PA14_RF_SSN") (class "Default")
      (node (ref "M1") (pin "21") (pinfunction "NSS_21") (pintype "bidirectional"))
      (node (ref "R14") (pin "1") (pinfunction "1_1") (pintype "passive"))
      (node (ref "U1") (pin "23") (pinfunction "PA14_23") (pintype "bidirectional"))
    )
    (net (code "43") (name "PA15_MISO") (class "Default")
      (node (ref "M1") (pin "20") (pinfunction "MISO_20") (pintype "bidirectional"))
      (node (ref "U1") (pin "24") (pinfunction "PA15_24") (pintype "bidirectional"))
    )
    (net (code "44") (name "PA16_S1_MOSI") (class "Default")
      (node (ref "J5") (pin "3") (pinfunction "3_3") (pintype "passive"))
      (node (ref "U1") (pin "25") (pinfunction "PA16_25") (pintype "bidirectional"))
    )
    (net (code "45") (name "PA17_S1_SCK") (class "Default")
      (node (ref "J5") (pin "4") (pinfunction "4_4") (pintype "passive"))
      (node (ref "U1") (pin "26") (pinfunction "PA17_26") (pintype "bidirectional"))
    )
    (net (code "46") (name "PA18_USB_ID") (class "Default")
      (node (ref "D2") (pin "A") (pinfunction "A_A") (pintype "passive"))
      (node (ref "U1") (pin "27") (pinfunction "PA18_27") (pintype "bidirectional"))
    )
    (net (code "47") (name "PA19_S1_MISO") (class "Default")
      (node (ref "J5") (pin "5") (pinfunction "5_5") (pintype "passive"))
      (node (ref "U1") (pin "28") (pinfunction "PA19_28") (pintype "bidirectional"))
    )
    (net (code "48") (name "PA20_TCC0-W6") (class "Default")
      (node (ref "J5") (pin "1") (pinfunction "1_1") (pintype "passive"))
      (node (ref "Q8") (pin "G") (pinfunction "G_G") (pintype "passive"))
      (node (ref "R33") (pin "2") (pinfunction "2_2") (pintype "passive"))
      (node (ref "U1") (pin "29") (pinfunction "PA20_29") (pintype "bidirectional"))
    )
    (net (code "49") (name "PA21_TCC0-W7") (class "Default")
      (node (ref "J5") (pin "2") (pinfunction "2_2") (pintype "passive"))
      (node (ref "U1") (pin "30") (pinfunction "PA21_30") (pintype "bidirectional"))
    )
    (net (code "50") (name "PA22_TC4-W0") (class "Default")
      (node (ref "J3") (pin "9") (pinfunction "9_9") (pintype "passive"))
      (node (ref "U1") (pin "31") (pinfunction "PA22_31") (pintype "bidirectional"))
    )
    (net (code "51") (name "PA23_TC4-W1") (class "Default")
      (node (ref "J3") (pin "10") (pinfunction "10_10") (pintype "passive"))
      (node (ref "U1") (pin "32") (pinfunction "PA23_32") (pintype "bidirectional"))
    )
    (net (code "52") (name "PA27_RF_NRES") (class "Default")
      (node (ref "M1") (pin "9") (pinfunction "PC0_9") (pintype "bidirectional"))
      (node (ref "U1") (pin "39") (pinfunction "PA27_39") (pintype "bidirectional"))
    )
    (net (code "53") (name "PA28_RF_PWRON") (class "Default")
      (node (ref "M1") (pin "24") (pinfunction "PB4_24") (pintype "bidirectional"))
      (node (ref "U1") (pin "41") (pinfunction "PA28_41") (pintype "bidirectional"))
    )
    (net (code "54") (name "PA30_SWCLK") (class "Default")
      (node (ref "J2") (pin "4") (pinfunction "4_4") (pintype "passive"))
      (node (ref "R4") (pin "1") (pinfunction "1_1") (pintype "passive"))
      (node (ref "U1") (pin "45") (pinfunction "PA30/SWCLK_45") (pintype "bidirectional"))
    )
    (net (code "55") (name "PA31_SWDIO") (class "Default")
      (node (ref "J2") (pin "2") (pinfunction "2_2") (pintype "passive"))
      (node (ref "U1") (pin "46") (pinfunction "PA31/SWDIO_46") (pintype "bidirectional"))
    )
    (net (code "56") (name "PB02_AIN10") (class "Default")
      (node (ref "J3") (pin "3") (pinfunction "3_3") (pintype "passive"))
      (node (ref "U1") (pin "47") (pinfunction "PB02_47") (pintype "bidirectional"))
    )
    (net (code "57") (name "PB03_AIN11") (class "Default")
      (node (ref "J3") (pin "4") (pinfunction "4_4") (pintype "passive"))
      (node (ref "U1") (pin "48") (pinfunction "PB03_48") (pintype "bidirectional"))
    )
    (net (code "58") (name "PB08_AIN3") (class "Default")
      (node (ref "C8") (pin "1") (pinfunction "1_1") (pintype "passive"))
      (node (ref "R8") (pin "2") (pinfunction "2_2") (pintype "passive"))
      (node (ref "R9") (pin "1") (pinfunction "1_1") (pintype "passive"))
      (node (ref "U1") (pin "7") (pinfunction "PB08_7") (pintype "bidirectional"))
    )
    (net (code "59") (name "PB09_RF_EVENT") (class "Default")
      (node (ref "M1") (pin "25") (pinfunction "PB6_25") (pintype "bidirectional"))
      (node (ref "U1") (pin "8") (pinfunction "PB09_8") (pintype "bidirectional"))
    )
    (net (code "60") (name "PB10_TCC0-W4") (class "Default")
      (node (ref "J3") (pin "13") (pinfunction "13_13") (pintype "passive"))
      (node (ref "U1") (pin "19") (pinfunction "PB10_19") (pintype "bidirectional"))
    )
    (net (code "61") (name "PB11_TCC0-W5") (class "Default")
      (node (ref "J3") (pin "14") (pinfunction "14_14") (pintype "passive"))
      (node (ref "U1") (pin "20") (pinfunction "PB11_20") (pintype "bidirectional"))
    )
    (net (code "62") (name "PB22_S5_TX") (class "Default")
      (node (ref "J5") (pin "9") (pinfunction "9_9") (pintype "passive"))
      (node (ref "U1") (pin "37") (pinfunction "PB22_37") (pintype "bidirectional"))
    )
    (net (code "63") (name "PB23_S5_RX") (class "Default")
      (node (ref "J5") (pin "8") (pinfunction "8_8") (pintype "passive"))
      (node (ref "U1") (pin "38") (pinfunction "PB23_38") (pintype "bidirectional"))
    )
    (net (code "64") (name "RESET#") (class "Default")
      (node (ref "J5") (pin "10") (pinfunction "10_10") (pintype "passive"))
      (node (ref "R6") (pin "2") (pinfunction "2_2") (pintype "passive"))
    )
    (net (code "65") (name "RESETN") (class "Default")
      (node (ref "C3") (pin "1") (pinfunction "1_1") (pintype "passive"))
      (node (ref "R2") (pin "2") (pinfunction "2_2") (pintype "passive"))
      (node (ref "R3") (pin "2") (pinfunction "2_2") (pintype "passive"))
      (node (ref "R5") (pin "1") (pinfunction "1_1") (pintype "passive"))
      (node (ref "R6") (pin "1") (pinfunction "1_1") (pintype "passive"))
      (node (ref "U1") (pin "40") (pinfunction "RESETN_40") (pintype "bidirectional"))
    )
    (net (code "66") (name "USB_ID") (class "Default")
      (node (ref "D2") (pin "C") (pinfunction "C_C") (pintype "passive"))
      (node (ref "D3") (pin "C") (pinfunction "C_C") (pintype "passive"))
      (node (ref "J1") (pin "4") (pinfunction "4_4") (pintype "passive"))
      (node (ref "USB_ID") (pin "X") (pinfunction "TESTP_X") (pintype "passive"))
    )
    (net (code "67") (name "USB_N") (class "Default")
      (node (ref "D-") (pin "X") (pinfunction "TESTP_X") (pintype "passive"))
      (node (ref "D1") (pin "3") (pinfunction "3_3") (pintype "passive"))
      (node (ref "J1") (pin "2") (pinfunction "2_2") (pintype "passive"))
      (node (ref "U1") (pin "33") (pinfunction "PA24/USB_DM_33") (pintype "bidirectional"))
    )
    (net (code "68") (name "USB_P") (class "Default")
      (node (ref "D+") (pin "X") (pinfunction "TESTP_X") (pintype "passive"))
      (node (ref "D1") (pin "2") (pinfunction "2_2") (pintype "passive"))
      (node (ref "J1") (pin "3") (pinfunction "3_3") (pintype "passive"))
      (node (ref "U1") (pin "34") (pinfunction "PA25/USB_DP_34") (pintype "bidirectional"))
    )
    (net (code "69") (name "VBATT") (class "Default")
      (node (ref "Q6") (pin "D1") (pinfunction "D_D1") (pintype "passive"))
      (node (ref "Q6") (pin "D1'") (pinfunction "D_D1'") (pintype "passive"))
      (node (ref "R9") (pin "2") (pinfunction "2_2") (pintype "passive"))
      (node (ref "TP4") (pin "X") (pinfunction "TESTP_X") (pintype "passive"))
      (node (ref "X1") (pin "V+") (pinfunction "V+_V+") (pintype "passive"))
    )
    (net (code "70") (name "VIN") (class "Default")
      (node (ref "J5") (pin "13") (pinfunction "13_13") (pintype "passive"))
      (node (ref "Q2") (pin "D1") (pinfunction "D_D1") (pintype "passive"))
      (node (ref "Q2") (pin "D1'") (pinfunction "D_D1'") (pintype "passive"))
      (node (ref "R23") (pin "2") (pinfunction "2_2") (pintype "passive"))
    )
    (net (code "71") (name "VUSB") (class "Default")
      (node (ref "C6") (pin "1") (pinfunction "1_1") (pintype "passive"))
      (node (ref "L1") (pin "2") (pinfunction "2_2") (pintype "passive"))
      (node (ref "Q1") (pin "D1") (pinfunction "D_D1") (pintype "passive"))
      (node (ref "Q1") (pin "D1'") (pinfunction "D_D1'") (pintype "passive"))
      (node (ref "R25") (pin "2") (pinfunction "2_2") (pintype "passive"))
    )
    (net (code "72") (name "unconnected-(J2-Pad6)") (class "Default")
      (node (ref "J2") (pin "6") (pinfunction "6_6") (pintype "passive"))
    )
    (net (code "73") (name "unconnected-(M1A-PB0-Pad17)") (class "Default")
      (node (ref "M1") (pin "17") (pinfunction "PB0_17") (pintype "bidirectional"))
    )
    (net (code "74") (name "unconnected-(M1A-PB7-Pad26)") (class "Default")
      (node (ref "M1") (pin "26") (pinfunction "PB7_26") (pintype "bidirectional"))
    )
    (net (code "75") (name "unconnected-(M1A-PC1-Pad10)") (class "Default")
      (node (ref "M1") (pin "10") (pinfunction "PC1_10") (pintype "bidirectional"))
    )
    (net (code "76") (name "unconnected-(M1A-PC2-Pad11)") (class "Default")
      (node (ref "M1") (pin "11") (pinfunction "PC2_11") (pintype "bidirectional"))
    )
    (net (code "77") (name "unconnected-(M1A-PC3-Pad14)") (class "Default")
      (node (ref "M1") (pin "14") (pinfunction "PC3_14") (pintype "bidirectional"))
    )
    (net (code "78") (name "unconnected-(M1A-PC4-Pad15)") (class "Default")
      (node (ref "M1") (pin "15") (pinfunction "PC4_15") (pintype "bidirectional"))
    )
    (net (code "79") (name "unconnected-(M1A-PC5-Pad16)") (class "Default")
      (node (ref "M1") (pin "16") (pinfunction "PC5_16") (pintype "bidirectional"))
    )
    (net (code "80") (name "unconnected-(M1B-NC-Pad6)") (class "Default")
      (node (ref "M1") (pin "6") (pinfunction "NC_6") (pintype "no_connect"))
    )
    (net (code "81") (name "unconnected-(M1B-NC-Pad7)") (class "Default")
      (node (ref "M1") (pin "7") (pinfunction "NC_7") (pintype "no_connect"))
    )
    (net (code "82") (name "unconnected-(M1B-NC-Pad28)") (class "Default")
      (node (ref "M1") (pin "28") (pinfunction "NC_28") (pintype "no_connect"))
    )
    (net (code "83") (name "unconnected-(M1B-NC-Pad29)") (class "Default")
      (node (ref "M1") (pin "29") (pinfunction "NC_29") (pintype "no_connect"))
    )
  )
)
